# stairs.net
KiCad netlist of a schematic drawn in EAGLE
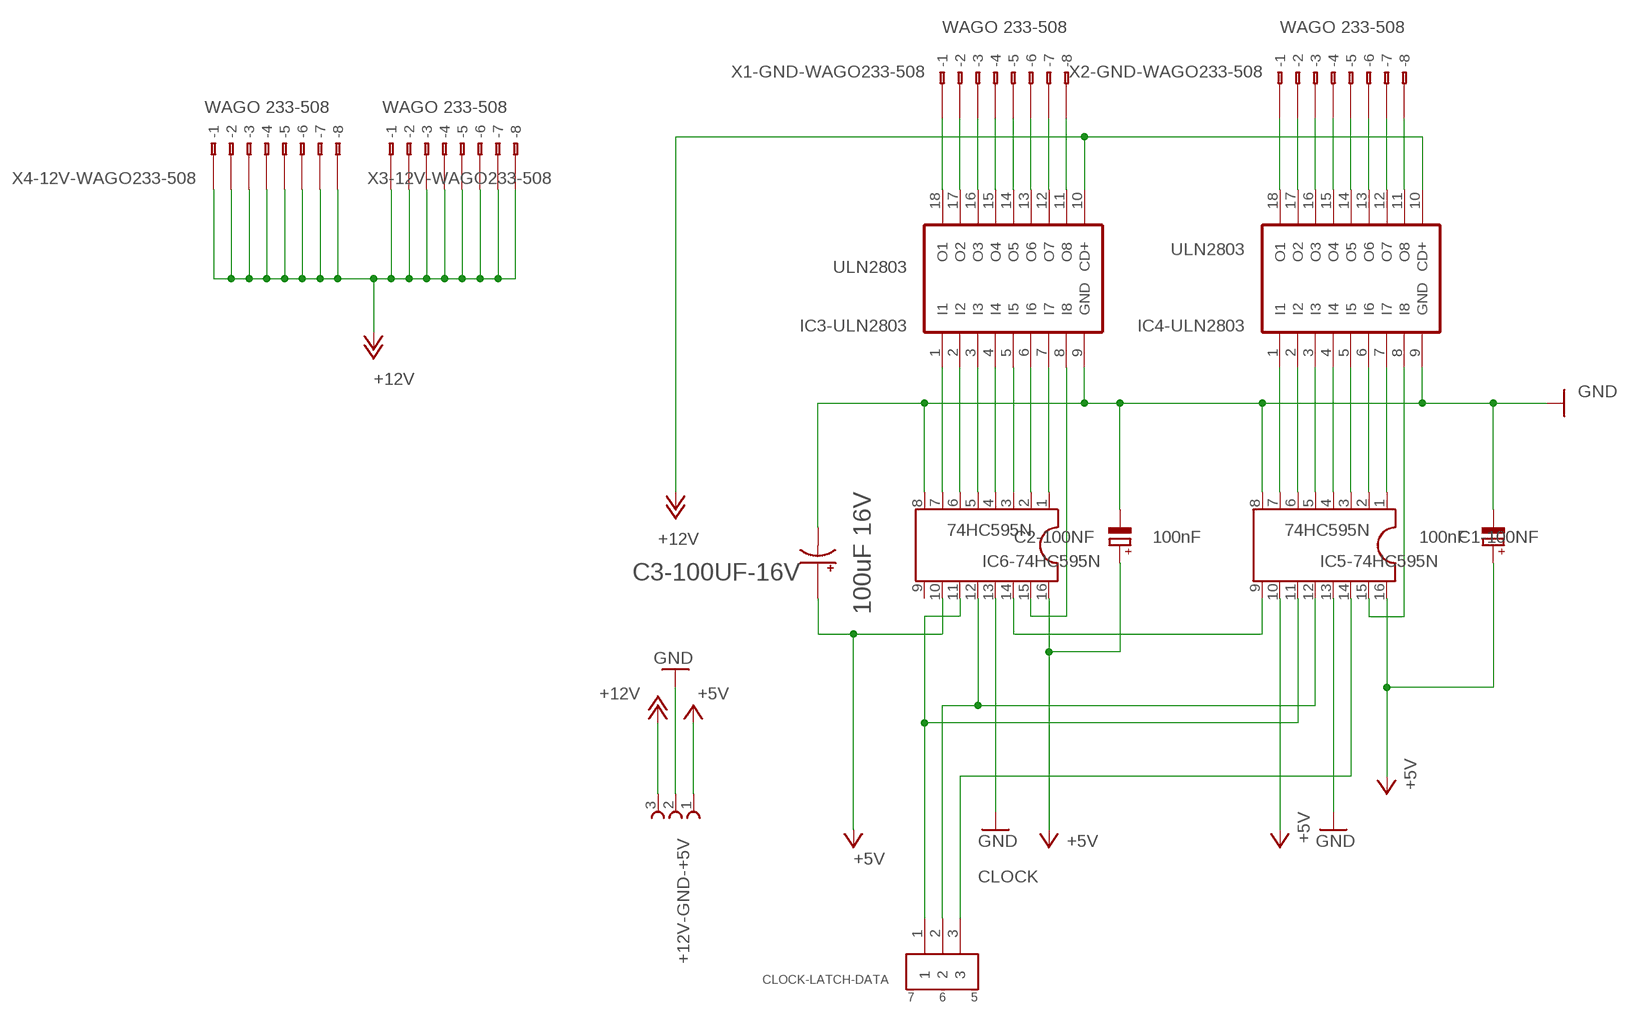
[diagram p0: schematic, sheet 1]

(export (version "E")
  (design (tool "Eeschema 10.0.6"))
  (components
    (comp (ref "+12V-GND-+5V")
      (value "+12V GND +5V")
      (footprint "eagle-import:691212710003")
      (fields (field (name "MF") "Wurth Electronics") (field (name "MP") "691212710003"))
      (libsource (lib "eagle-import") (part "691212710003"))
    )
    (comp (ref "C1-100NF")
      (value "100nF")
      (footprint "eagle-import:E2,5-6E")
      (libsource (lib "eagle-import") (part "CPOL-EUE2,5-6E"))
    )
    (comp (ref "C2-100NF")
      (value "100nF")
      (footprint "eagle-import:E2,5-6E")
      (libsource (lib "eagle-import") (part "CPOL-EUE2,5-6E"))
    )
    (comp (ref "C3-100UF-16V")
      (value "100uF 16V")
      (footprint "eagle-import:CAPPRD200W50D500H1000")
      (fields (field (name "MF") "Nichicon") (field (name "MP") "RNE1C101MDS1PX"))
      (libsource (lib "eagle-import") (part "RNE1C101MDS1PX"))
    )
    (comp (ref "CLOCK-LATCH-DATA")
      (value "7 6 5")
      (footprint "eagle-import:MOLEX_0022272031")
      (fields (field (name "MF") "Molex, LLC") (field (name "MP") "0022272031"))
      (libsource (lib "eagle-import") (part "0022272031"))
    )
    (comp (ref "IC3-ULN2803")
      (value "ULN2803")
      (footprint "eagle-import:DIL18")
      (libsource (lib "eagle-import") (part "ULN2803A"))
    )
    (comp (ref "IC4-ULN2803")
      (value "ULN2803")
      (footprint "eagle-import:DIL18")
      (libsource (lib "eagle-import") (part "ULN2803A"))
    )
    (comp (ref "IC5-74HC595N")
      (value "74HC595N")
      (footprint "eagle-import:DIL16")
      (libsource (lib "eagle-import") (part "DIL16"))
    )
    (comp (ref "IC6-74HC595N")
      (value "74HC595N")
      (footprint "eagle-import:DIL16")
      (libsource (lib "eagle-import") (part "DIL16"))
    )
    (comp (ref "X1-GND-WAGO233-508")
      (value "WAGO 233-508")
      (footprint "eagle-import:233-508")
      (fields (field (name "MF") "WAGO") (field (name "MP") "233-508"))
      (libsource (lib "eagle-import") (part "233-508"))
    )
    (comp (ref "X2-GND-WAGO233-508")
      (value "WAGO 233-508")
      (footprint "eagle-import:233-508")
      (fields (field (name "MF") "WAGO") (field (name "MP") "233-508"))
      (libsource (lib "eagle-import") (part "233-508"))
    )
    (comp (ref "X3-12V-WAGO233-508")
      (value "WAGO 233-508")
      (footprint "eagle-import:233-508")
      (fields (field (name "MF") "Wago Corporation") (field (name "MPN") "0233-0508"))
      (libsource (lib "eagle-import") (part "con-wago_197_233-508"))
    )
    (comp (ref "X4-12V-WAGO233-508")
      (value "WAGO 233-508")
      (footprint "eagle-import:233-508")
      (fields (field (name "MF") "Wago Corporation") (field (name "MPN") "0233-0508"))
      (libsource (lib "eagle-import") (part "con-wago_197_233-508"))
    )
  )
  (nets
    (net (code "1") (name "+5V") (class "Default")
      (node (ref "+12V-GND-+5V") (pin "1") (pinfunction "1_1") (pintype "passive"))
      (node (ref "C1-100NF") (pin "+") (pinfunction "+_+") (pintype "passive"))
      (node (ref "C2-100NF") (pin "+") (pinfunction "+_+") (pintype "passive"))
      (node (ref "C3-100UF-16V") (pin "1") (pinfunction "P_1") (pintype "passive"))
      (node (ref "IC5-74HC595N") (pin "10") (pinfunction "10_10") (pintype "passive"))
      (node (ref "IC5-74HC595N") (pin "16") (pinfunction "16_16") (pintype "passive"))
      (node (ref "IC6-74HC595N") (pin "10") (pinfunction "10_10") (pintype "passive"))
      (node (ref "IC6-74HC595N") (pin "16") (pinfunction "16_16") (pintype "passive"))
    )
    (net (code "2") (name "+12V") (class "Default")
      (node (ref "+12V-GND-+5V") (pin "3") (pinfunction "3_3") (pintype "passive"))
      (node (ref "IC3-ULN2803") (pin "10") (pinfunction "CD+_10") (pintype "passive"))
      (node (ref "IC4-ULN2803") (pin "10") (pinfunction "CD+_10") (pintype "passive"))
      (node (ref "X3-12V-WAGO233-508") (pin "B1") (pinfunction "B-1_B1") (pintype "passive"))
      (node (ref "X3-12V-WAGO233-508") (pin "B2") (pinfunction "B-2_B2") (pintype "passive"))
      (node (ref "X3-12V-WAGO233-508") (pin "B3") (pinfunction "B-3_B3") (pintype "passive"))
      (node (ref "X3-12V-WAGO233-508") (pin "B4") (pinfunction "B-4_B4") (pintype "passive"))
      (node (ref "X3-12V-WAGO233-508") (pin "B5") (pinfunction "B-5_B5") (pintype "passive"))
      (node (ref "X3-12V-WAGO233-508") (pin "B6") (pinfunction "B-6_B6") (pintype "passive"))
      (node (ref "X3-12V-WAGO233-508") (pin "B7") (pinfunction "B-7_B7") (pintype "passive"))
      (node (ref "X3-12V-WAGO233-508") (pin "B8") (pinfunction "B-8_B8") (pintype "passive"))
      (node (ref "X4-12V-WAGO233-508") (pin "B1") (pinfunction "B-1_B1") (pintype "passive"))
      (node (ref "X4-12V-WAGO233-508") (pin "B2") (pinfunction "B-2_B2") (pintype "passive"))
      (node (ref "X4-12V-WAGO233-508") (pin "B3") (pinfunction "B-3_B3") (pintype "passive"))
      (node (ref "X4-12V-WAGO233-508") (pin "B4") (pinfunction "B-4_B4") (pintype "passive"))
      (node (ref "X4-12V-WAGO233-508") (pin "B5") (pinfunction "B-5_B5") (pintype "passive"))
      (node (ref "X4-12V-WAGO233-508") (pin "B6") (pinfunction "B-6_B6") (pintype "passive"))
      (node (ref "X4-12V-WAGO233-508") (pin "B7") (pinfunction "B-7_B7") (pintype "passive"))
      (node (ref "X4-12V-WAGO233-508") (pin "B8") (pinfunction "B-8_B8") (pintype "passive"))
    )
    (net (code "3") (name "/CLOCK") (class "Default")
      (node (ref "CLOCK-LATCH-DATA") (pin "3") (pinfunction "3_3") (pintype "passive"))
      (node (ref "IC5-74HC595N") (pin "14") (pinfunction "14_14") (pintype "passive"))
    )
    (net (code "4") (name "GND") (class "Default")
      (node (ref "+12V-GND-+5V") (pin "2") (pinfunction "2_2") (pintype "passive"))
      (node (ref "C1-100NF") (pin "-") (pinfunction "-_-") (pintype "passive"))
      (node (ref "C2-100NF") (pin "-") (pinfunction "-_-") (pintype "passive"))
      (node (ref "C3-100UF-16V") (pin "2") (pinfunction "N_2") (pintype "passive"))
      (node (ref "IC3-ULN2803") (pin "9") (pinfunction "GND_9") (pintype "power_in"))
      (node (ref "IC4-ULN2803") (pin "9") (pinfunction "GND_9") (pintype "power_in"))
      (node (ref "IC5-74HC595N") (pin "13") (pinfunction "13_13") (pintype "passive"))
      (node (ref "IC5-74HC595N") (pin "8") (pinfunction "8_8") (pintype "passive"))
      (node (ref "IC6-74HC595N") (pin "13") (pinfunction "13_13") (pintype "passive"))
      (node (ref "IC6-74HC595N") (pin "8") (pinfunction "8_8") (pintype "passive"))
    )
    (net (code "5") (name "Net-(CLOCK-LATCH-DATA-Pad1)") (class "Default")
      (node (ref "CLOCK-LATCH-DATA") (pin "1") (pinfunction "1_1") (pintype "passive"))
      (node (ref "IC5-74HC595N") (pin "11") (pinfunction "11_11") (pintype "passive"))
      (node (ref "IC6-74HC595N") (pin "11") (pinfunction "11_11") (pintype "passive"))
    )
    (net (code "6") (name "Net-(CLOCK-LATCH-DATA-Pad2)") (class "Default")
      (node (ref "CLOCK-LATCH-DATA") (pin "2") (pinfunction "2_2") (pintype "passive"))
      (node (ref "IC5-74HC595N") (pin "12") (pinfunction "12_12") (pintype "passive"))
      (node (ref "IC6-74HC595N") (pin "12") (pinfunction "12_12") (pintype "passive"))
    )
    (net (code "7") (name "Net-(IC3-ULN2803-I1)") (class "Default")
      (node (ref "IC3-ULN2803") (pin "1") (pinfunction "I1_1") (pintype "input"))
      (node (ref "IC6-74HC595N") (pin "7") (pinfunction "7_7") (pintype "passive"))
    )
    (net (code "8") (name "Net-(IC3-ULN2803-I2)") (class "Default")
      (node (ref "IC3-ULN2803") (pin "2") (pinfunction "I2_2") (pintype "input"))
      (node (ref "IC6-74HC595N") (pin "6") (pinfunction "6_6") (pintype "passive"))
    )
    (net (code "9") (name "Net-(IC3-ULN2803-I3)") (class "Default")
      (node (ref "IC3-ULN2803") (pin "3") (pinfunction "I3_3") (pintype "input"))
      (node (ref "IC6-74HC595N") (pin "5") (pinfunction "5_5") (pintype "passive"))
    )
    (net (code "10") (name "Net-(IC3-ULN2803-I4)") (class "Default")
      (node (ref "IC3-ULN2803") (pin "4") (pinfunction "I4_4") (pintype "input"))
      (node (ref "IC6-74HC595N") (pin "4") (pinfunction "4_4") (pintype "passive"))
    )
    (net (code "11") (name "Net-(IC3-ULN2803-I5)") (class "Default")
      (node (ref "IC3-ULN2803") (pin "5") (pinfunction "I5_5") (pintype "input"))
      (node (ref "IC6-74HC595N") (pin "3") (pinfunction "3_3") (pintype "passive"))
    )
    (net (code "12") (name "Net-(IC3-ULN2803-I6)") (class "Default")
      (node (ref "IC3-ULN2803") (pin "6") (pinfunction "I6_6") (pintype "input"))
      (node (ref "IC6-74HC595N") (pin "2") (pinfunction "2_2") (pintype "passive"))
    )
    (net (code "13") (name "Net-(IC3-ULN2803-I7)") (class "Default")
      (node (ref "IC3-ULN2803") (pin "7") (pinfunction "I7_7") (pintype "input"))
      (node (ref "IC6-74HC595N") (pin "1") (pinfunction "1_1") (pintype "passive"))
    )
    (net (code "14") (name "Net-(IC3-ULN2803-I8)") (class "Default")
      (node (ref "IC3-ULN2803") (pin "8") (pinfunction "I8_8") (pintype "input"))
      (node (ref "IC6-74HC595N") (pin "15") (pinfunction "15_15") (pintype "passive"))
    )
    (net (code "15") (name "Net-(IC3-ULN2803-O1)") (class "Default")
      (node (ref "IC3-ULN2803") (pin "18") (pinfunction "O1_18") (pintype "open_collector"))
      (node (ref "X1-GND-WAGO233-508") (pin "B1") (pinfunction "B-1_B1") (pintype "passive"))
    )
    (net (code "16") (name "Net-(IC3-ULN2803-O2)") (class "Default")
      (node (ref "IC3-ULN2803") (pin "17") (pinfunction "O2_17") (pintype "open_collector"))
      (node (ref "X1-GND-WAGO233-508") (pin "B2") (pinfunction "B-2_B2") (pintype "passive"))
    )
    (net (code "17") (name "Net-(IC3-ULN2803-O3)") (class "Default")
      (node (ref "IC3-ULN2803") (pin "16") (pinfunction "O3_16") (pintype "open_collector"))
      (node (ref "X1-GND-WAGO233-508") (pin "B3") (pinfunction "B-3_B3") (pintype "passive"))
    )
    (net (code "18") (name "Net-(IC3-ULN2803-O4)") (class "Default")
      (node (ref "IC3-ULN2803") (pin "15") (pinfunction "O4_15") (pintype "open_collector"))
      (node (ref "X1-GND-WAGO233-508") (pin "B4") (pinfunction "B-4_B4") (pintype "passive"))
    )
    (net (code "19") (name "Net-(IC3-ULN2803-O5)") (class "Default")
      (node (ref "IC3-ULN2803") (pin "14") (pinfunction "O5_14") (pintype "open_collector"))
      (node (ref "X1-GND-WAGO233-508") (pin "B5") (pinfunction "B-5_B5") (pintype "passive"))
    )
    (net (code "20") (name "Net-(IC3-ULN2803-O6)") (class "Default")
      (node (ref "IC3-ULN2803") (pin "13") (pinfunction "O6_13") (pintype "open_collector"))
      (node (ref "X1-GND-WAGO233-508") (pin "B6") (pinfunction "B-6_B6") (pintype "passive"))
    )
    (net (code "21") (name "Net-(IC3-ULN2803-O7)") (class "Default")
      (node (ref "IC3-ULN2803") (pin "12") (pinfunction "O7_12") (pintype "open_collector"))
      (node (ref "X1-GND-WAGO233-508") (pin "B7") (pinfunction "B-7_B7") (pintype "passive"))
    )
    (net (code "22") (name "Net-(IC3-ULN2803-O8)") (class "Default")
      (node (ref "IC3-ULN2803") (pin "11") (pinfunction "O8_11") (pintype "open_collector"))
      (node (ref "X1-GND-WAGO233-508") (pin "B8") (pinfunction "B-8_B8") (pintype "passive"))
    )
    (net (code "23") (name "Net-(IC4-ULN2803-I1)") (class "Default")
      (node (ref "IC4-ULN2803") (pin "1") (pinfunction "I1_1") (pintype "input"))
      (node (ref "IC5-74HC595N") (pin "7") (pinfunction "7_7") (pintype "passive"))
    )
    (net (code "24") (name "Net-(IC4-ULN2803-I2)") (class "Default")
      (node (ref "IC4-ULN2803") (pin "2") (pinfunction "I2_2") (pintype "input"))
      (node (ref "IC5-74HC595N") (pin "6") (pinfunction "6_6") (pintype "passive"))
    )
    (net (code "25") (name "Net-(IC4-ULN2803-I3)") (class "Default")
      (node (ref "IC4-ULN2803") (pin "3") (pinfunction "I3_3") (pintype "input"))
      (node (ref "IC5-74HC595N") (pin "5") (pinfunction "5_5") (pintype "passive"))
    )
    (net (code "26") (name "Net-(IC4-ULN2803-I4)") (class "Default")
      (node (ref "IC4-ULN2803") (pin "4") (pinfunction "I4_4") (pintype "input"))
      (node (ref "IC5-74HC595N") (pin "4") (pinfunction "4_4") (pintype "passive"))
    )
    (net (code "27") (name "Net-(IC4-ULN2803-I5)") (class "Default")
      (node (ref "IC4-ULN2803") (pin "5") (pinfunction "I5_5") (pintype "input"))
      (node (ref "IC5-74HC595N") (pin "3") (pinfunction "3_3") (pintype "passive"))
    )
    (net (code "28") (name "Net-(IC4-ULN2803-I6)") (class "Default")
      (node (ref "IC4-ULN2803") (pin "6") (pinfunction "I6_6") (pintype "input"))
      (node (ref "IC5-74HC595N") (pin "2") (pinfunction "2_2") (pintype "passive"))
    )
    (net (code "29") (name "Net-(IC4-ULN2803-I7)") (class "Default")
      (node (ref "IC4-ULN2803") (pin "7") (pinfunction "I7_7") (pintype "input"))
      (node (ref "IC5-74HC595N") (pin "1") (pinfunction "1_1") (pintype "passive"))
    )
    (net (code "30") (name "Net-(IC4-ULN2803-I8)") (class "Default")
      (node (ref "IC4-ULN2803") (pin "8") (pinfunction "I8_8") (pintype "input"))
      (node (ref "IC5-74HC595N") (pin "15") (pinfunction "15_15") (pintype "passive"))
    )
    (net (code "31") (name "Net-(IC4-ULN2803-O1)") (class "Default")
      (node (ref "IC4-ULN2803") (pin "18") (pinfunction "O1_18") (pintype "open_collector"))
      (node (ref "X2-GND-WAGO233-508") (pin "B1") (pinfunction "B-1_B1") (pintype "passive"))
    )
    (net (code "32") (name "Net-(IC4-ULN2803-O2)") (class "Default")
      (node (ref "IC4-ULN2803") (pin "17") (pinfunction "O2_17") (pintype "open_collector"))
      (node (ref "X2-GND-WAGO233-508") (pin "B2") (pinfunction "B-2_B2") (pintype "passive"))
    )
    (net (code "33") (name "Net-(IC4-ULN2803-O3)") (class "Default")
      (node (ref "IC4-ULN2803") (pin "16") (pinfunction "O3_16") (pintype "open_collector"))
      (node (ref "X2-GND-WAGO233-508") (pin "B3") (pinfunction "B-3_B3") (pintype "passive"))
    )
    (net (code "34") (name "Net-(IC4-ULN2803-O4)") (class "Default")
      (node (ref "IC4-ULN2803") (pin "15") (pinfunction "O4_15") (pintype "open_collector"))
      (node (ref "X2-GND-WAGO233-508") (pin "B4") (pinfunction "B-4_B4") (pintype "passive"))
    )
    (net (code "35") (name "Net-(IC4-ULN2803-O5)") (class "Default")
      (node (ref "IC4-ULN2803") (pin "14") (pinfunction "O5_14") (pintype "open_collector"))
      (node (ref "X2-GND-WAGO233-508") (pin "B5") (pinfunction "B-5_B5") (pintype "passive"))
    )
    (net (code "36") (name "Net-(IC4-ULN2803-O6)") (class "Default")
      (node (ref "IC4-ULN2803") (pin "13") (pinfunction "O6_13") (pintype "open_collector"))
      (node (ref "X2-GND-WAGO233-508") (pin "B6") (pinfunction "B-6_B6") (pintype "passive"))
    )
    (net (code "37") (name "Net-(IC4-ULN2803-O7)") (class "Default")
      (node (ref "IC4-ULN2803") (pin "12") (pinfunction "O7_12") (pintype "open_collector"))
      (node (ref "X2-GND-WAGO233-508") (pin "B7") (pinfunction "B-7_B7") (pintype "passive"))
    )
    (net (code "38") (name "Net-(IC4-ULN2803-O8)") (class "Default")
      (node (ref "IC4-ULN2803") (pin "11") (pinfunction "O8_11") (pintype "open_collector"))
      (node (ref "X2-GND-WAGO233-508") (pin "B8") (pinfunction "B-8_B8") (pintype "passive"))
    )
    (net (code "39") (name "Net-(IC5-74HC595N-Pad9)") (class "Default")
      (node (ref "IC5-74HC595N") (pin "9") (pinfunction "9_9") (pintype "passive"))
      (node (ref "IC6-74HC595N") (pin "14") (pinfunction "14_14") (pintype "passive"))
    )
    (net (code "40") (name "unconnected-(IC6-74HC595N-Pad9)") (class "Default")
      (node (ref "IC6-74HC595N") (pin "9") (pinfunction "9_9") (pintype "passive"))
    )
    (net (code "41") (name "unconnected-(X1-GND-WAGO233-508--1-PadA1)") (class "Default")
      (node (ref "X1-GND-WAGO233-508") (pin "A1") (pinfunction "-1_A1") (pintype "passive"))
    )
    (net (code "42") (name "unconnected-(X1-GND-WAGO233-508--2-PadA2)") (class "Default")
      (node (ref "X1-GND-WAGO233-508") (pin "A2") (pinfunction "-2_A2") (pintype "passive"))
    )
    (net (code "43") (name "unconnected-(X1-GND-WAGO233-508--3-PadA3)") (class "Default")
      (node (ref "X1-GND-WAGO233-508") (pin "A3") (pinfunction "-3_A3") (pintype "passive"))
    )
    (net (code "44") (name "unconnected-(X1-GND-WAGO233-508--4-PadA4)") (class "Default")
      (node (ref "X1-GND-WAGO233-508") (pin "A4") (pinfunction "-4_A4") (pintype "passive"))
    )
    (net (code "45") (name "unconnected-(X1-GND-WAGO233-508--5-PadA5)") (class "Default")
      (node (ref "X1-GND-WAGO233-508") (pin "A5") (pinfunction "-5_A5") (pintype "passive"))
    )
    (net (code "46") (name "unconnected-(X1-GND-WAGO233-508--6-PadA6)") (class "Default")
      (node (ref "X1-GND-WAGO233-508") (pin "A6") (pinfunction "-6_A6") (pintype "passive"))
    )
    (net (code "47") (name "unconnected-(X1-GND-WAGO233-508--7-PadA7)") (class "Default")
      (node (ref "X1-GND-WAGO233-508") (pin "A7") (pinfunction "-7_A7") (pintype "passive"))
    )
    (net (code "48") (name "unconnected-(X1-GND-WAGO233-508--8-PadA8)") (class "Default")
      (node (ref "X1-GND-WAGO233-508") (pin "A8") (pinfunction "-8_A8") (pintype "passive"))
    )
    (net (code "49") (name "unconnected-(X2-GND-WAGO233-508--1-PadA1)") (class "Default")
      (node (ref "X2-GND-WAGO233-508") (pin "A1") (pinfunction "-1_A1") (pintype "passive"))
    )
    (net (code "50") (name "unconnected-(X2-GND-WAGO233-508--2-PadA2)") (class "Default")
      (node (ref "X2-GND-WAGO233-508") (pin "A2") (pinfunction "-2_A2") (pintype "passive"))
    )
    (net (code "51") (name "unconnected-(X2-GND-WAGO233-508--3-PadA3)") (class "Default")
      (node (ref "X2-GND-WAGO233-508") (pin "A3") (pinfunction "-3_A3") (pintype "passive"))
    )
    (net (code "52") (name "unconnected-(X2-GND-WAGO233-508--4-PadA4)") (class "Default")
      (node (ref "X2-GND-WAGO233-508") (pin "A4") (pinfunction "-4_A4") (pintype "passive"))
    )
    (net (code "53") (name "unconnected-(X2-GND-WAGO233-508--5-PadA5)") (class "Default")
      (node (ref "X2-GND-WAGO233-508") (pin "A5") (pinfunction "-5_A5") (pintype "passive"))
    )
    (net (code "54") (name "unconnected-(X2-GND-WAGO233-508--6-PadA6)") (class "Default")
      (node (ref "X2-GND-WAGO233-508") (pin "A6") (pinfunction "-6_A6") (pintype "passive"))
    )
    (net (code "55") (name "unconnected-(X2-GND-WAGO233-508--7-PadA7)") (class "Default")
      (node (ref "X2-GND-WAGO233-508") (pin "A7") (pinfunction "-7_A7") (pintype "passive"))
    )
    (net (code "56") (name "unconnected-(X2-GND-WAGO233-508--8-PadA8)") (class "Default")
      (node (ref "X2-GND-WAGO233-508") (pin "A8") (pinfunction "-8_A8") (pintype "passive"))
    )
    (net (code "57") (name "unconnected-(X3-12V-WAGO233-508--1-PadA1)") (class "Default")
      (node (ref "X3-12V-WAGO233-508") (pin "A1") (pinfunction "-1_A1") (pintype "passive"))
    )
    (net (code "58") (name "unconnected-(X3-12V-WAGO233-508--2-PadA2)") (class "Default")
      (node (ref "X3-12V-WAGO233-508") (pin "A2") (pinfunction "-2_A2") (pintype "passive"))
    )
    (net (code "59") (name "unconnected-(X3-12V-WAGO233-508--3-PadA3)") (class "Default")
      (node (ref "X3-12V-WAGO233-508") (pin "A3") (pinfunction "-3_A3") (pintype "passive"))
    )
    (net (code "60") (name "unconnected-(X3-12V-WAGO233-508--4-PadA4)") (class "Default")
      (node (ref "X3-12V-WAGO233-508") (pin "A4") (pinfunction "-4_A4") (pintype "passive"))
    )
    (net (code "61") (name "unconnected-(X3-12V-WAGO233-508--5-PadA5)") (class "Default")
      (node (ref "X3-12V-WAGO233-508") (pin "A5") (pinfunction "-5_A5") (pintype "passive"))
    )
    (net (code "62") (name "unconnected-(X3-12V-WAGO233-508--6-PadA6)") (class "Default")
      (node (ref "X3-12V-WAGO233-508") (pin "A6") (pinfunction "-6_A6") (pintype "passive"))
    )
    (net (code "63") (name "unconnected-(X3-12V-WAGO233-508--7-PadA7)") (class "Default")
      (node (ref "X3-12V-WAGO233-508") (pin "A7") (pinfunction "-7_A7") (pintype "passive"))
    )
    (net (code "64") (name "unconnected-(X3-12V-WAGO233-508--8-PadA8)") (class "Default")
      (node (ref "X3-12V-WAGO233-508") (pin "A8") (pinfunction "-8_A8") (pintype "passive"))
    )
    (net (code "65") (name "unconnected-(X4-12V-WAGO233-508--1-PadA1)") (class "Default")
      (node (ref "X4-12V-WAGO233-508") (pin "A1") (pinfunction "-1_A1") (pintype "passive"))
    )
    (net (code "66") (name "unconnected-(X4-12V-WAGO233-508--2-PadA2)") (class "Default")
      (node (ref "X4-12V-WAGO233-508") (pin "A2") (pinfunction "-2_A2") (pintype "passive"))
    )
    (net (code "67") (name "unconnected-(X4-12V-WAGO233-508--3-PadA3)") (class "Default")
      (node (ref "X4-12V-WAGO233-508") (pin "A3") (pinfunction "-3_A3") (pintype "passive"))
    )
    (net (code "68") (name "unconnected-(X4-12V-WAGO233-508--4-PadA4)") (class "Default")
      (node (ref "X4-12V-WAGO233-508") (pin "A4") (pinfunction "-4_A4") (pintype "passive"))
    )
    (net (code "69") (name "unconnected-(X4-12V-WAGO233-508--5-PadA5)") (class "Default")
      (node (ref "X4-12V-WAGO233-508") (pin "A5") (pinfunction "-5_A5") (pintype "passive"))
    )
    (net (code "70") (name "unconnected-(X4-12V-WAGO233-508--6-PadA6)") (class "Default")
      (node (ref "X4-12V-WAGO233-508") (pin "A6") (pinfunction "-6_A6") (pintype "passive"))
    )
    (net (code "71") (name "unconnected-(X4-12V-WAGO233-508--7-PadA7)") (class "Default")
      (node (ref "X4-12V-WAGO233-508") (pin "A7") (pinfunction "-7_A7") (pintype "passive"))
    )
    (net (code "72") (name "unconnected-(X4-12V-WAGO233-508--8-PadA8)") (class "Default")
      (node (ref "X4-12V-WAGO233-508") (pin "A8") (pinfunction "-8_A8") (pintype "passive"))
    )
  )
)
